# DRV8432_MotorControler.net
KiCad netlist of a schematic drawn in Altium Designer
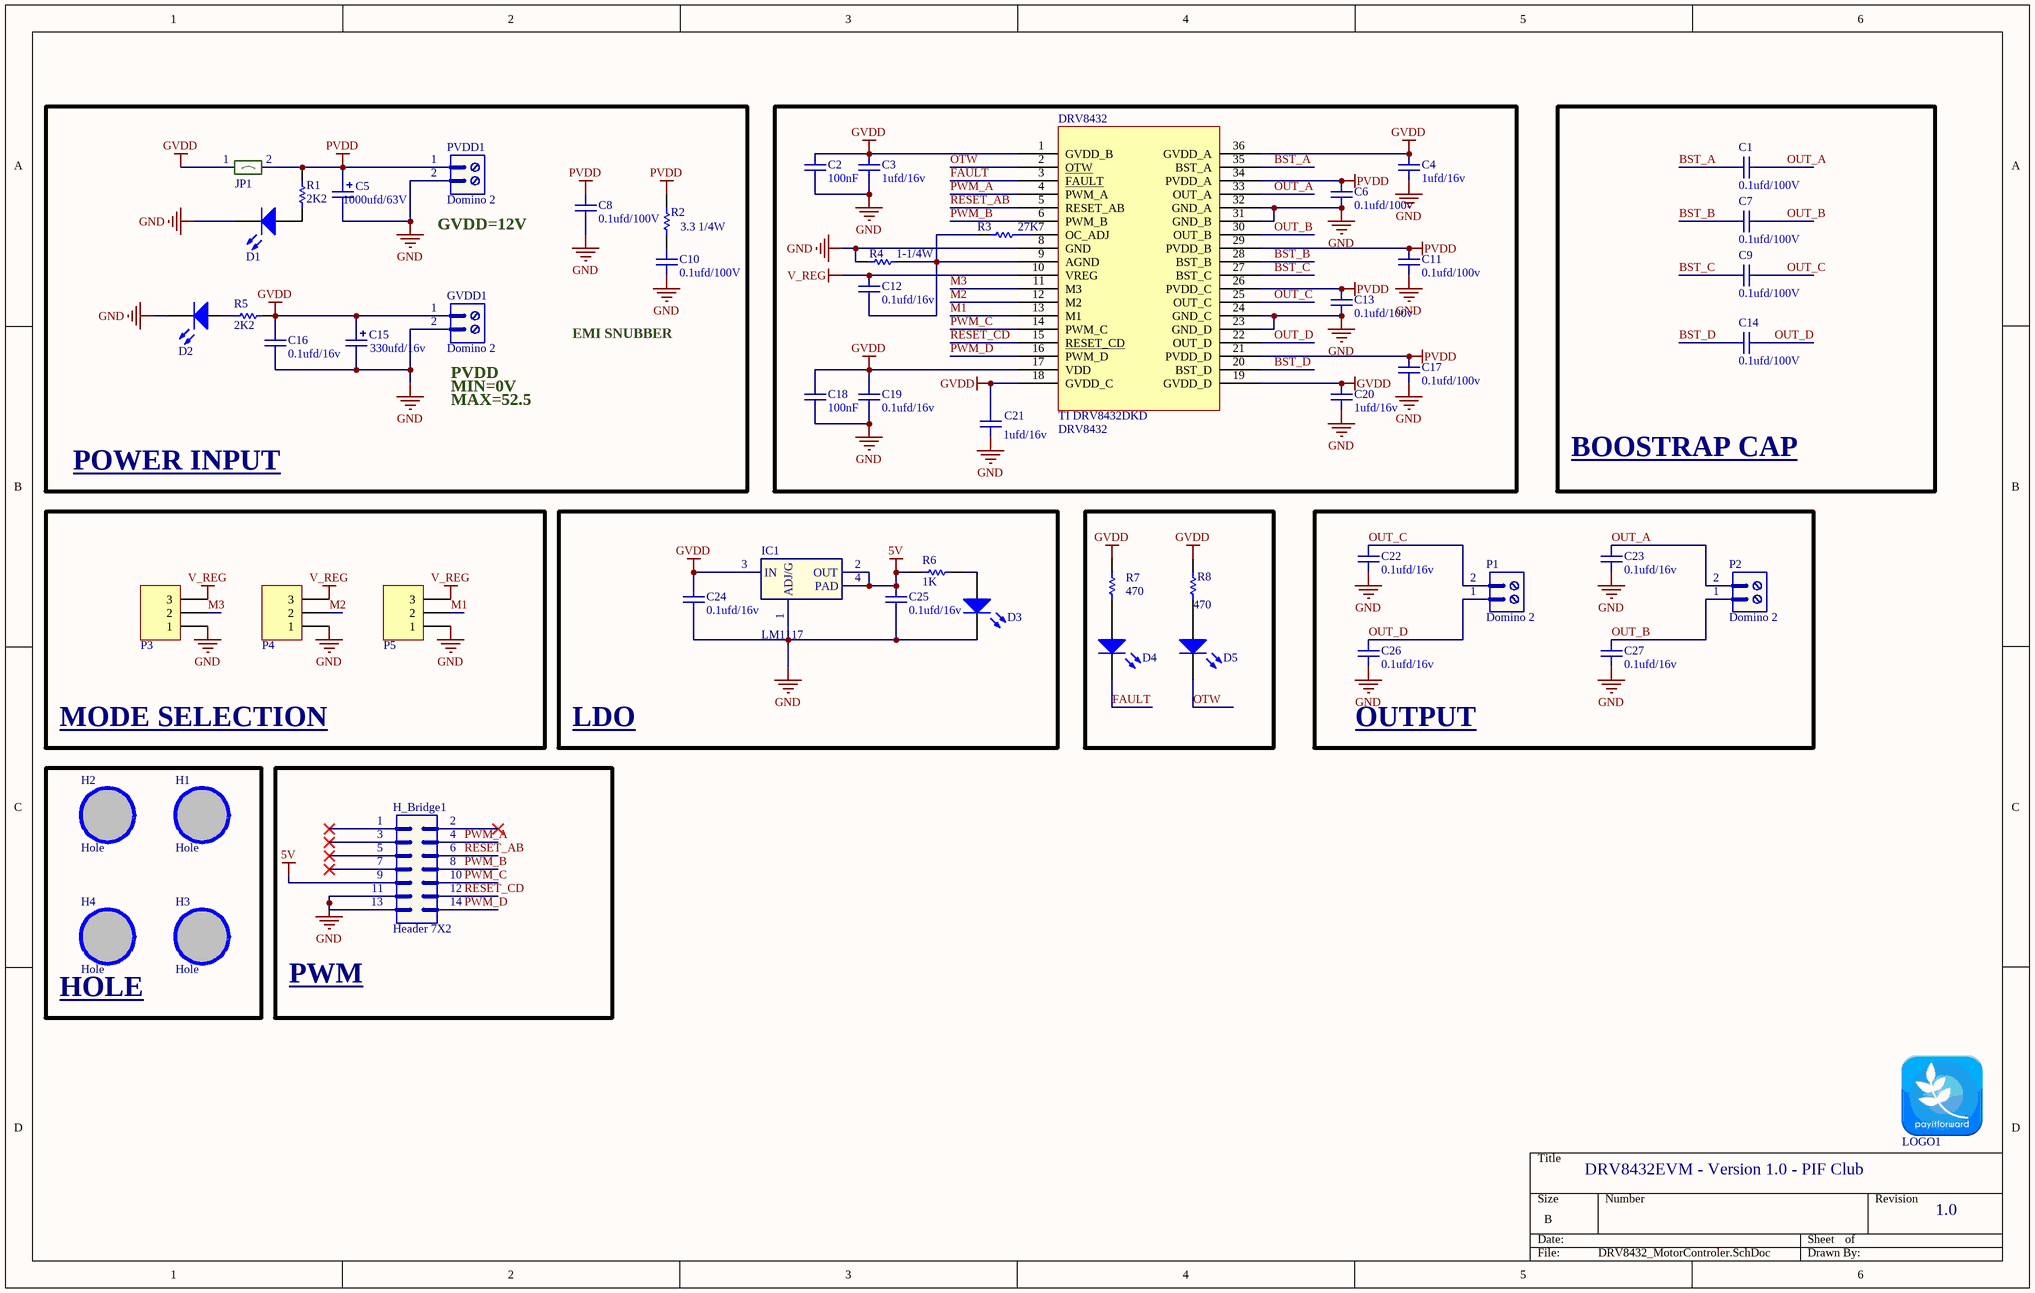
[diagram p0: DRV8432_MotorControler.SchDoc]

(export (version "E")
  (design (tool "Eeschema 10.0.6"))
  (components
    (comp (ref "C1")
      (value "0.1ufd/100V")
      (footprint "CAP-SM-0805")
      (description "Capacitor")
      (fields (field (name "Comment") "Cap Non-Pol SMD"))
      (libsource (lib "minht57_lib") (part "Cap Non-Pol SMD"))
    )
    (comp (ref "C2")
      (value "100nF")
      (footprint "CAP-SM-1210")
      (description "Capacitor")
      (fields (field (name "Comment") "Cap Non-Pol SMD"))
      (libsource (lib "minht57_lib") (part "Cap Non-Pol SMD"))
    )
    (comp (ref "C3")
      (value "1ufd/16v")
      (footprint "CAP-SM-0603")
      (description "Capacitor")
      (fields (field (name "Comment") "Cap Non-Pol SMD"))
      (libsource (lib "minht57_lib") (part "Cap Non-Pol SMD"))
    )
    (comp (ref "C4")
      (value "1ufd/16v")
      (footprint "CAP-SM-0603")
      (description "Capacitor")
      (fields (field (name "Comment") "Cap Non-Pol SMD"))
      (libsource (lib "minht57_lib") (part "Cap Non-Pol SMD"))
    )
    (comp (ref "C5")
      (value "1000ufd/63V")
      (footprint "CP3/7")
      (description "Polarized Capacitor (Radial)")
      (fields (field (name "Comment") "Cap Pol"))
      (libsource (lib "minht57_lib") (part "Cap Pol"))
    )
    (comp (ref "C6")
      (value "0.1ufd/100v")
      (footprint "CAP-SM-0805")
      (description "Capacitor")
      (fields (field (name "Comment") "Cap Non-Pol SMD"))
      (libsource (lib "minht57_lib") (part "Cap Non-Pol SMD"))
    )
    (comp (ref "C7")
      (value "0.1ufd/100V")
      (footprint "CAP-SM-0805")
      (description "Capacitor")
      (fields (field (name "Comment") "Cap Non-Pol SMD"))
      (libsource (lib "minht57_lib") (part "Cap Non-Pol SMD"))
    )
    (comp (ref "C8")
      (value "0.1ufd/100V")
      (footprint "CAP-SM-0805")
      (description "Capacitor")
      (fields (field (name "Comment") "Cap Non-Pol SMD"))
      (libsource (lib "minht57_lib") (part "Cap Non-Pol SMD"))
    )
    (comp (ref "C9")
      (value "0.1ufd/100V")
      (footprint "CAP-SM-0805")
      (description "Capacitor")
      (fields (field (name "Comment") "Cap Non-Pol SMD"))
      (libsource (lib "minht57_lib") (part "Cap Non-Pol SMD"))
    )
    (comp (ref "C10")
      (value "0.1ufd/100V")
      (footprint "CAP-SM-0805")
      (description "Capacitor")
      (fields (field (name "Comment") "Cap Non-Pol SMD"))
      (libsource (lib "minht57_lib") (part "Cap Non-Pol SMD"))
    )
    (comp (ref "C11")
      (value "0.1ufd/100v")
      (footprint "CAP-SM-0805")
      (description "Capacitor")
      (fields (field (name "Comment") "Cap Non-Pol SMD"))
      (libsource (lib "minht57_lib") (part "Cap Non-Pol SMD"))
    )
    (comp (ref "C12")
      (value "0.1ufd/16v")
      (footprint "CAP-SM-0603")
      (description "Capacitor")
      (fields (field (name "Comment") "Cap Non-Pol SMD"))
      (libsource (lib "minht57_lib") (part "Cap Non-Pol SMD"))
    )
    (comp (ref "C13")
      (value "0.1ufd/100v")
      (footprint "CAP-SM-0805")
      (description "Capacitor")
      (fields (field (name "Comment") "Cap Non-Pol SMD"))
      (libsource (lib "minht57_lib") (part "Cap Non-Pol SMD"))
    )
    (comp (ref "C14")
      (value "0.1ufd/100V")
      (footprint "CAP-SM-0805")
      (description "Capacitor")
      (fields (field (name "Comment") "Cap Non-Pol SMD"))
      (libsource (lib "minht57_lib") (part "Cap Non-Pol SMD"))
    )
    (comp (ref "C15")
      (value "330ufd/16v")
      (footprint "CP1/2.5")
      (description "Polarized Capacitor (Radial)")
      (fields (field (name "Comment") "Cap Pol"))
      (libsource (lib "minht57_lib") (part "Cap Pol"))
    )
    (comp (ref "C16")
      (value "0.1ufd/16v")
      (footprint "CAP-SM-0805")
      (description "Capacitor")
      (fields (field (name "Comment") "Cap Non-Pol SMD"))
      (libsource (lib "minht57_lib") (part "Cap Non-Pol SMD"))
    )
    (comp (ref "C17")
      (value "0.1ufd/100v")
      (footprint "CAP-SM-0805")
      (description "Capacitor")
      (fields (field (name "Comment") "Cap Non-Pol SMD"))
      (libsource (lib "minht57_lib") (part "Cap Non-Pol SMD"))
    )
    (comp (ref "C18")
      (value "100nF")
      (footprint "CAP-SM-1210")
      (description "Capacitor")
      (fields (field (name "Comment") "Cap Non-Pol SMD"))
      (libsource (lib "minht57_lib") (part "Cap Non-Pol SMD"))
    )
    (comp (ref "C19")
      (value "0.1ufd/16v")
      (footprint "CAP-SM-0805")
      (description "Capacitor")
      (fields (field (name "Comment") "Cap Non-Pol SMD"))
      (libsource (lib "minht57_lib") (part "Cap Non-Pol SMD"))
    )
    (comp (ref "C20")
      (value "1ufd/16v")
      (footprint "CAP-SM-0603")
      (description "Capacitor")
      (fields (field (name "Comment") "Cap Non-Pol SMD"))
      (libsource (lib "minht57_lib") (part "Cap Non-Pol SMD"))
    )
    (comp (ref "C21")
      (value "1ufd/16v")
      (footprint "CAP-SM-0603")
      (description "Capacitor")
      (fields (field (name "Comment") "Cap Non-Pol SMD"))
      (libsource (lib "minht57_lib") (part "Cap Non-Pol SMD"))
    )
    (comp (ref "C22")
      (value "0.1ufd/16v")
      (footprint "CAP-SM-0805")
      (description "Capacitor")
      (fields (field (name "Comment") "Cap Non-Pol SMD"))
      (libsource (lib "minht57_lib") (part "Cap Non-Pol SMD"))
    )
    (comp (ref "C23")
      (value "0.1ufd/16v")
      (footprint "CAP-SM-0805")
      (description "Capacitor")
      (fields (field (name "Comment") "Cap Non-Pol SMD"))
      (libsource (lib "minht57_lib") (part "Cap Non-Pol SMD"))
    )
    (comp (ref "C24")
      (value "0.1ufd/16v")
      (footprint "CAP-SM-0805")
      (description "Capacitor")
      (fields (field (name "Comment") "Cap Non-Pol SMD"))
      (libsource (lib "minht57_lib") (part "Cap Non-Pol SMD"))
    )
    (comp (ref "C25")
      (value "0.1ufd/16v")
      (footprint "CAP-SM-0805")
      (description "Capacitor")
      (fields (field (name "Comment") "Cap Non-Pol SMD"))
      (libsource (lib "minht57_lib") (part "Cap Non-Pol SMD"))
    )
    (comp (ref "C26")
      (value "0.1ufd/16v")
      (footprint "CAP-SM-0805")
      (description "Capacitor")
      (fields (field (name "Comment") "Cap Non-Pol SMD"))
      (libsource (lib "minht57_lib") (part "Cap Non-Pol SMD"))
    )
    (comp (ref "C27")
      (value "0.1ufd/16v")
      (footprint "CAP-SM-0805")
      (description "Capacitor")
      (fields (field (name "Comment") "Cap Non-Pol SMD"))
      (libsource (lib "minht57_lib") (part "Cap Non-Pol SMD"))
    )
    (comp (ref "D1")
      (value "LED SMD")
      (footprint "LED_0603_Blue")
      (description "LED")
      (libsource (lib "PIF_Library") (part "LED SMD"))
    )
    (comp (ref "D2")
      (value "LED SMD")
      (footprint "LED_0603_Blue")
      (description "LED")
      (libsource (lib "PIF_Library") (part "LED SMD"))
    )
    (comp (ref "D3")
      (value "LED SMD")
      (footprint "LED_0603_Blue")
      (description "LED")
      (libsource (lib "PIF_Library") (part "LED SMD"))
    )
    (comp (ref "D4")
      (value "LED SMD")
      (footprint "LED_0603_Blue")
      (description "LED")
      (libsource (lib "PIF_Library") (part "LED SMD"))
    )
    (comp (ref "D5")
      (value "LED SMD")
      (footprint "LED_0603_Blue")
      (description "LED")
      (libsource (lib "PIF_Library") (part "LED SMD"))
    )
    (comp (ref "DRV8432")
      (value "DRV8432")
      (footprint "PCBComponent_1")
      (libsource (lib "TI_DRV8432") (part "Component_1"))
    )
    (comp (ref "GVDD1")
      (value "Domino 2")
      (footprint "DOMINO 2- 5mm")
      (description "Domino, 2-Pin")
      (fields (field (name "PUBLISHER") "Altium Limited"))
      (libsource (lib "") (part "Domino 2_1"))
    )
    (comp (ref "H1")
      (value "Hole")
      (footprint "LO KHOAN 3MM")
      (description "Hole 3mm")
      (libsource (lib "minht57_lib") (part "Hole"))
    )
    (comp (ref "H2")
      (value "Hole")
      (footprint "LO KHOAN 3MM")
      (description "Hole 3mm")
      (libsource (lib "minht57_lib") (part "Hole"))
    )
    (comp (ref "H3")
      (value "Hole")
      (footprint "LO KHOAN 3MM")
      (description "Hole 3mm")
      (libsource (lib "minht57_lib") (part "Hole"))
    )
    (comp (ref "H4")
      (value "Hole")
      (footprint "LO KHOAN 3MM")
      (description "Hole 3mm")
      (libsource (lib "minht57_lib") (part "Hole"))
    )
    (comp (ref "H_Bridge1")
      (value "Header 7X2")
      (footprint "JP7X2")
      (description "Header, 7-Pin, Dual row")
      (fields (field (name "PUBLISHER") "Altium Limited"))
      (libsource (lib "minht57_lib") (part "Header 7X2"))
    )
    (comp (ref "IC1")
      (value "LM1117")
      (footprint "SOT223-4N")
      (description "Available in 1.8V, 2.5V, 2.85V, 3.3V, 5V, and  Adjustable Versions")
      (libsource (lib "minht57_lib") (part "LM1117"))
    )
    (comp (ref "JP1") (value "Jumper 2") (footprint "JP2") (libsource (lib "minht57_lib") (part "Jumper 2")))
    (comp (ref "LOGO1")
      (value "LOGO PIF")
      (footprint "PIF LOGO TOP OVERLAY")
      (libsource (lib "logo_PIF") (part "LOGO PIF"))
    )
    (comp (ref "P1")
      (value "Domino 2")
      (footprint "DOMINO 2- 5mm")
      (description "Domino, 2-Pin")
      (fields (field (name "PUBLISHER") "Altium Limited"))
      (libsource (lib "minht57_lib") (part "Domino 2"))
    )
    (comp (ref "P2")
      (value "Domino 2")
      (footprint "DOMINO 2- 5mm")
      (description "Domino, 2-Pin")
      (fields (field (name "PUBLISHER") "Altium Limited"))
      (libsource (lib "minht57_lib") (part "Domino 2"))
    )
    (comp (ref "P3")
      (value "Header 3")
      (footprint "JP3")
      (description "Header, 3-Pin")
      (fields (field (name "PUBLISHER") "Altium Limited"))
      (libsource (lib "PIF_Library") (part "Header 3"))
    )
    (comp (ref "P4")
      (value "Header 3")
      (footprint "JP3")
      (description "Header, 3-Pin")
      (fields (field (name "PUBLISHER") "Altium Limited"))
      (libsource (lib "PIF_Library") (part "Header 3"))
    )
    (comp (ref "P5")
      (value "Header 3")
      (footprint "JP3")
      (description "Header, 3-Pin")
      (fields (field (name "PUBLISHER") "Altium Limited"))
      (libsource (lib "PIF_Library") (part "Header 3"))
    )
    (comp (ref "PVDD1")
      (value "Domino 2")
      (footprint "DOMINO 2- 5mm")
      (description "Domino, 2-Pin")
      (fields (field (name "PUBLISHER") "Altium Limited"))
      (libsource (lib "") (part "Domino 2_1"))
    )
    (comp (ref "R1")
      (value "2K2")
      (footprint "RES-SM-0603")
      (description "Resistor")
      (fields (field (name "Comment") "RESISTOR SMD"))
      (libsource (lib "PIF_Library") (part "RESISTOR SMD"))
    )
    (comp (ref "R2")
      (value "3.3 1/4W")
      (footprint "RES-SM-1206")
      (description "Resistor")
      (fields (field (name "Comment") "RESISTOR SMD"))
      (libsource (lib "PIF_Library") (part "RESISTOR SMD"))
    )
    (comp (ref "R3")
      (value "27K")
      (footprint "RES-SM-0603")
      (description "Resistor")
      (fields (field (name "Comment") "RESISTOR SMD"))
      (libsource (lib "PIF_Library") (part "RESISTOR SMD"))
    )
    (comp (ref "R4")
      (value "1-1/4W")
      (footprint "RES-SM-0805")
      (description "Resistor")
      (fields (field (name "Comment") "RESISTOR SMD"))
      (libsource (lib "PIF_Library") (part "RESISTOR SMD"))
    )
    (comp (ref "R5")
      (value "2K2")
      (footprint "RES-SM-0603")
      (description "Resistor")
      (fields (field (name "Comment") "RESISTOR SMD"))
      (libsource (lib "PIF_Library") (part "RESISTOR SMD"))
    )
    (comp (ref "R6")
      (value "1K")
      (footprint "RES-SM-0603")
      (description "Resistor")
      (fields (field (name "Comment") "RESISTOR SMD"))
      (libsource (lib "PIF_Library") (part "RESISTOR SMD"))
    )
    (comp (ref "R7")
      (value "470")
      (footprint "RES-SM-0603")
      (description "Resistor")
      (fields (field (name "Comment") "RESISTOR SMD"))
      (libsource (lib "PIF_Library") (part "RESISTOR SMD"))
    )
    (comp (ref "R8")
      (value "470")
      (footprint "RES-SM-0603")
      (description "Resistor")
      (fields (field (name "Comment") "RESISTOR SMD"))
      (libsource (lib "PIF_Library") (part "RESISTOR SMD"))
    )
  )
  (nets
    (net (code "1") (name "/BST_A") (class "Default")
      (node (ref "C1") (pin "1") (pinfunction "1_1") (pintype "passive"))
      (node (ref "DRV8432") (pin "35") (pinfunction "BST_A_35") (pintype "passive"))
    )
    (net (code "2") (name "/BST_B") (class "Default")
      (node (ref "C7") (pin "1") (pinfunction "1_1") (pintype "passive"))
      (node (ref "DRV8432") (pin "28") (pinfunction "BST_B_28") (pintype "passive"))
    )
    (net (code "3") (name "/BST_C") (class "Default")
      (node (ref "C9") (pin "1") (pinfunction "1_1") (pintype "passive"))
      (node (ref "DRV8432") (pin "27") (pinfunction "BST_C_27") (pintype "passive"))
    )
    (net (code "4") (name "/BST_D") (class "Default")
      (node (ref "C14") (pin "1") (pinfunction "1_1") (pintype "passive"))
      (node (ref "DRV8432") (pin "20") (pinfunction "BST_D_20") (pintype "passive"))
    )
    (net (code "5") (name "/FAULT") (class "Default")
      (node (ref "D4") (pin "2") (pinfunction "K_2") (pintype "passive"))
      (node (ref "DRV8432") (pin "3") (pinfunction "FAULT_3") (pintype "passive"))
    )
    (net (code "6") (name "/M1") (class "Default")
      (node (ref "DRV8432") (pin "13") (pinfunction "M1_13") (pintype "passive"))
      (node (ref "P5") (pin "2") (pinfunction "2_2") (pintype "passive"))
    )
    (net (code "7") (name "/M2") (class "Default")
      (node (ref "DRV8432") (pin "12") (pinfunction "M2_12") (pintype "passive"))
      (node (ref "P4") (pin "2") (pinfunction "2_2") (pintype "passive"))
    )
    (net (code "8") (name "/M3") (class "Default")
      (node (ref "DRV8432") (pin "11") (pinfunction "M3_11") (pintype "passive"))
      (node (ref "P3") (pin "2") (pinfunction "2_2") (pintype "passive"))
    )
    (net (code "9") (name "/OTW") (class "Default")
      (node (ref "D5") (pin "2") (pinfunction "K_2") (pintype "passive"))
      (node (ref "DRV8432") (pin "2") (pinfunction "OTW_2") (pintype "passive"))
    )
    (net (code "10") (name "/OUT_A") (class "Default")
      (node (ref "C1") (pin "2") (pinfunction "2_2") (pintype "passive"))
      (node (ref "C23") (pin "2") (pinfunction "2_2") (pintype "passive"))
      (node (ref "DRV8432") (pin "33") (pinfunction "OUT_A_33") (pintype "passive"))
      (node (ref "P2") (pin "2") (pinfunction "2_2") (pintype "passive"))
    )
    (net (code "11") (name "/OUT_B") (class "Default")
      (node (ref "C27") (pin "2") (pinfunction "2_2") (pintype "passive"))
      (node (ref "C7") (pin "2") (pinfunction "2_2") (pintype "passive"))
      (node (ref "DRV8432") (pin "30") (pinfunction "OUT_B_30") (pintype "passive"))
      (node (ref "P2") (pin "1") (pinfunction "1_1") (pintype "passive"))
    )
    (net (code "12") (name "/OUT_C") (class "Default")
      (node (ref "C22") (pin "2") (pinfunction "2_2") (pintype "passive"))
      (node (ref "C9") (pin "2") (pinfunction "2_2") (pintype "passive"))
      (node (ref "DRV8432") (pin "25") (pinfunction "OUT_C_25") (pintype "passive"))
      (node (ref "P1") (pin "2") (pinfunction "2_2") (pintype "passive"))
    )
    (net (code "13") (name "/OUT_D") (class "Default")
      (node (ref "C14") (pin "2") (pinfunction "2_2") (pintype "passive"))
      (node (ref "C26") (pin "2") (pinfunction "2_2") (pintype "passive"))
      (node (ref "DRV8432") (pin "22") (pinfunction "OUT_D_22") (pintype "passive"))
      (node (ref "P1") (pin "1") (pinfunction "1_1") (pintype "passive"))
    )
    (net (code "14") (name "/PWM_A") (class "Default")
      (node (ref "DRV8432") (pin "4") (pinfunction "PWM_A_4") (pintype "passive"))
      (node (ref "H_Bridge1") (pin "4") (pinfunction "4_4") (pintype "passive"))
    )
    (net (code "15") (name "/PWM_B") (class "Default")
      (node (ref "DRV8432") (pin "6") (pinfunction "PWM_B_6") (pintype "passive"))
      (node (ref "H_Bridge1") (pin "8") (pinfunction "8_8") (pintype "passive"))
    )
    (net (code "16") (name "/PWM_C") (class "Default")
      (node (ref "DRV8432") (pin "14") (pinfunction "PWM_C_14") (pintype "passive"))
      (node (ref "H_Bridge1") (pin "10") (pinfunction "10_10") (pintype "passive"))
    )
    (net (code "17") (name "/PWM_D") (class "Default")
      (node (ref "DRV8432") (pin "16") (pinfunction "PWM_D_16") (pintype "passive"))
      (node (ref "H_Bridge1") (pin "14") (pinfunction "14_14") (pintype "passive"))
    )
    (net (code "18") (name "/RESET_AB") (class "Default")
      (node (ref "DRV8432") (pin "5") (pinfunction "RESET_AB_5") (pintype "passive"))
      (node (ref "H_Bridge1") (pin "6") (pinfunction "6_6") (pintype "passive"))
    )
    (net (code "19") (name "/RESET_CD") (class "Default")
      (node (ref "DRV8432") (pin "15") (pinfunction "RESET_CD_15") (pintype "passive"))
      (node (ref "H_Bridge1") (pin "12") (pinfunction "12_12") (pintype "passive"))
    )
    (net (code "20") (name "5V") (class "Default")
      (node (ref "C25") (pin "2") (pinfunction "2_2") (pintype "passive"))
      (node (ref "H_Bridge1") (pin "9") (pinfunction "9_9") (pintype "passive"))
      (node (ref "IC1") (pin "2") (pinfunction "OUT_2") (pintype "passive"))
      (node (ref "IC1") (pin "4") (pinfunction "PAD_4") (pintype "passive"))
      (node (ref "R6") (pin "2") (pinfunction "2_2") (pintype "passive"))
    )
    (net (code "21") (name "GND") (class "Default")
      (node (ref "C10") (pin "1") (pinfunction "1_1") (pintype "passive"))
      (node (ref "C11") (pin "1") (pinfunction "1_1") (pintype "passive"))
      (node (ref "C13") (pin "1") (pinfunction "1_1") (pintype "passive"))
      (node (ref "C15") (pin "2") (pinfunction "2_2") (pintype "passive"))
      (node (ref "C16") (pin "1") (pinfunction "1_1") (pintype "passive"))
      (node (ref "C17") (pin "1") (pinfunction "1_1") (pintype "passive"))
      (node (ref "C18") (pin "1") (pinfunction "1_1") (pintype "passive"))
      (node (ref "C19") (pin "1") (pinfunction "1_1") (pintype "passive"))
      (node (ref "C2") (pin "1") (pinfunction "1_1") (pintype "passive"))
      (node (ref "C20") (pin "1") (pinfunction "1_1") (pintype "passive"))
      (node (ref "C21") (pin "1") (pinfunction "1_1") (pintype "passive"))
      (node (ref "C22") (pin "1") (pinfunction "1_1") (pintype "passive"))
      (node (ref "C23") (pin "1") (pinfunction "1_1") (pintype "passive"))
      (node (ref "C24") (pin "1") (pinfunction "1_1") (pintype "passive"))
      (node (ref "C25") (pin "1") (pinfunction "1_1") (pintype "passive"))
      (node (ref "C26") (pin "1") (pinfunction "1_1") (pintype "passive"))
      (node (ref "C27") (pin "1") (pinfunction "1_1") (pintype "passive"))
      (node (ref "C3") (pin "2") (pinfunction "2_2") (pintype "passive"))
      (node (ref "C4") (pin "2") (pinfunction "2_2") (pintype "passive"))
      (node (ref "C5") (pin "2") (pinfunction "2_2") (pintype "passive"))
      (node (ref "C6") (pin "1") (pinfunction "1_1") (pintype "passive"))
      (node (ref "C8") (pin "1") (pinfunction "1_1") (pintype "passive"))
      (node (ref "D1") (pin "2") (pinfunction "K_2") (pintype "passive"))
      (node (ref "D2") (pin "2") (pinfunction "K_2") (pintype "passive"))
      (node (ref "D3") (pin "2") (pinfunction "K_2") (pintype "passive"))
      (node (ref "DRV8432") (pin "23") (pinfunction "GND_D_23") (pintype "passive"))
      (node (ref "DRV8432") (pin "24") (pinfunction "GND_C_24") (pintype "passive"))
      (node (ref "DRV8432") (pin "31") (pinfunction "GND_B_31") (pintype "passive"))
      (node (ref "DRV8432") (pin "32") (pinfunction "GND_A_32") (pintype "passive"))
      (node (ref "DRV8432") (pin "8") (pinfunction "GND_8") (pintype "passive"))
      (node (ref "GVDD1") (pin "2") (pinfunction "2_2") (pintype "passive"))
      (node (ref "H_Bridge1") (pin "11") (pinfunction "11_11") (pintype "passive"))
      (node (ref "H_Bridge1") (pin "13") (pinfunction "13_13") (pintype "passive"))
      (node (ref "IC1") (pin "1") (pinfunction "ADJ/G_1") (pintype "passive"))
      (node (ref "P3") (pin "1") (pinfunction "1_1") (pintype "passive"))
      (node (ref "P4") (pin "1") (pinfunction "1_1") (pintype "passive"))
      (node (ref "P5") (pin "1") (pinfunction "1_1") (pintype "passive"))
      (node (ref "PVDD1") (pin "2") (pinfunction "2_2") (pintype "passive"))
      (node (ref "R4") (pin "2") (pinfunction "2_2") (pintype "passive"))
    )
    (net (code "22") (name "GVDD") (class "Default")
      (node (ref "C15") (pin "1") (pinfunction "1_1") (pintype "passive"))
      (node (ref "C16") (pin "2") (pinfunction "2_2") (pintype "passive"))
      (node (ref "C18") (pin "2") (pinfunction "2_2") (pintype "passive"))
      (node (ref "C19") (pin "2") (pinfunction "2_2") (pintype "passive"))
      (node (ref "C2") (pin "2") (pinfunction "2_2") (pintype "passive"))
      (node (ref "C20") (pin "2") (pinfunction "2_2") (pintype "passive"))
      (node (ref "C21") (pin "2") (pinfunction "2_2") (pintype "passive"))
      (node (ref "C24") (pin "2") (pinfunction "2_2") (pintype "passive"))
      (node (ref "C3") (pin "1") (pinfunction "1_1") (pintype "passive"))
      (node (ref "C4") (pin "1") (pinfunction "1_1") (pintype "passive"))
      (node (ref "DRV8432") (pin "1") (pinfunction "GVDD_B_1") (pintype "passive"))
      (node (ref "DRV8432") (pin "17") (pinfunction "VDD_17") (pintype "passive"))
      (node (ref "DRV8432") (pin "18") (pinfunction "GVDD_C_18") (pintype "passive"))
      (node (ref "DRV8432") (pin "19") (pinfunction "GVDD_D_19") (pintype "passive"))
      (node (ref "DRV8432") (pin "36") (pinfunction "GVDD_A_36") (pintype "passive"))
      (node (ref "GVDD1") (pin "1") (pinfunction "1_1") (pintype "passive"))
      (node (ref "IC1") (pin "3") (pinfunction "IN_3") (pintype "passive"))
      (node (ref "JP1") (pin "1") (pinfunction "1_1") (pintype "passive"))
      (node (ref "R5") (pin "2") (pinfunction "2_2") (pintype "passive"))
      (node (ref "R7") (pin "2") (pinfunction "2_2") (pintype "passive"))
      (node (ref "R8") (pin "2") (pinfunction "2_2") (pintype "passive"))
    )
    (net (code "23") (name "Net-(C10-Pad2)") (class "Default")
      (node (ref "C10") (pin "2") (pinfunction "2_2") (pintype "passive"))
      (node (ref "R2") (pin "1") (pinfunction "1_1") (pintype "passive"))
    )
    (net (code "24") (name "Net-(D1-A)") (class "Default")
      (node (ref "D1") (pin "1") (pinfunction "A_1") (pintype "passive"))
      (node (ref "R1") (pin "1") (pinfunction "1_1") (pintype "passive"))
    )
    (net (code "25") (name "Net-(D2-A)") (class "Default")
      (node (ref "D2") (pin "1") (pinfunction "A_1") (pintype "passive"))
      (node (ref "R5") (pin "1") (pinfunction "1_1") (pintype "passive"))
    )
    (net (code "26") (name "Net-(D3-A)") (class "Default")
      (node (ref "D3") (pin "1") (pinfunction "A_1") (pintype "passive"))
      (node (ref "R6") (pin "1") (pinfunction "1_1") (pintype "passive"))
    )
    (net (code "27") (name "Net-(D4-A)") (class "Default")
      (node (ref "D4") (pin "1") (pinfunction "A_1") (pintype "passive"))
      (node (ref "R7") (pin "1") (pinfunction "1_1") (pintype "passive"))
    )
    (net (code "28") (name "Net-(D5-A)") (class "Default")
      (node (ref "D5") (pin "1") (pinfunction "A_1") (pintype "passive"))
      (node (ref "R8") (pin "1") (pinfunction "1_1") (pintype "passive"))
    )
    (net (code "29") (name "Net-(DRV8432-AGND)") (class "Default")
      (node (ref "C12") (pin "2") (pinfunction "2_2") (pintype "passive"))
      (node (ref "DRV8432") (pin "9") (pinfunction "AGND_9") (pintype "passive"))
      (node (ref "R3") (pin "2") (pinfunction "2_2") (pintype "passive"))
      (node (ref "R4") (pin "1") (pinfunction "1_1") (pintype "passive"))
    )
    (net (code "30") (name "Net-(DRV8432-OC_ADJ)") (class "Default")
      (node (ref "DRV8432") (pin "7") (pinfunction "OC_ADJ_7") (pintype "passive"))
      (node (ref "R3") (pin "1") (pinfunction "1_1") (pintype "passive"))
    )
    (net (code "31") (name "PVDD") (class "Default")
      (node (ref "C11") (pin "2") (pinfunction "2_2") (pintype "passive"))
      (node (ref "C13") (pin "2") (pinfunction "2_2") (pintype "passive"))
      (node (ref "C17") (pin "2") (pinfunction "2_2") (pintype "passive"))
      (node (ref "C5") (pin "1") (pinfunction "1_1") (pintype "passive"))
      (node (ref "C6") (pin "2") (pinfunction "2_2") (pintype "passive"))
      (node (ref "C8") (pin "2") (pinfunction "2_2") (pintype "passive"))
      (node (ref "DRV8432") (pin "21") (pinfunction "PVDD_D_21") (pintype "passive"))
      (node (ref "DRV8432") (pin "26") (pinfunction "PVDD_C_26") (pintype "passive"))
      (node (ref "DRV8432") (pin "29") (pinfunction "PVDD_B_29") (pintype "passive"))
      (node (ref "DRV8432") (pin "34") (pinfunction "PVDD_A_34") (pintype "passive"))
      (node (ref "JP1") (pin "2") (pinfunction "2_2") (pintype "passive"))
      (node (ref "PVDD1") (pin "1") (pinfunction "1_1") (pintype "passive"))
      (node (ref "R1") (pin "2") (pinfunction "2_2") (pintype "passive"))
      (node (ref "R2") (pin "2") (pinfunction "2_2") (pintype "passive"))
    )
    (net (code "32") (name "V_REG") (class "Default")
      (node (ref "C12") (pin "1") (pinfunction "1_1") (pintype "passive"))
      (node (ref "DRV8432") (pin "10") (pinfunction "VREG_10") (pintype "passive"))
      (node (ref "P3") (pin "3") (pinfunction "3_3") (pintype "passive"))
      (node (ref "P4") (pin "3") (pinfunction "3_3") (pintype "passive"))
      (node (ref "P5") (pin "3") (pinfunction "3_3") (pintype "passive"))
    )
    (net (code "33") (name "unconnected-(H1-Pad1)") (class "Default")
      (node (ref "H1") (pin "1") (pinfunction "1_1") (pintype "passive"))
    )
    (net (code "34") (name "unconnected-(H2-Pad1)") (class "Default")
      (node (ref "H2") (pin "1") (pinfunction "1_1") (pintype "passive"))
    )
    (net (code "35") (name "unconnected-(H3-Pad1)") (class "Default")
      (node (ref "H3") (pin "1") (pinfunction "1_1") (pintype "passive"))
    )
    (net (code "36") (name "unconnected-(H4-Pad1)") (class "Default")
      (node (ref "H4") (pin "1") (pinfunction "1_1") (pintype "passive"))
    )
    (net (code "37") (name "unconnected-(H_Bridge1-Pad1)") (class "Default")
      (node (ref "H_Bridge1") (pin "1") (pinfunction "1_1") (pintype "passive+no_connect"))
    )
    (net (code "38") (name "unconnected-(H_Bridge1-Pad2)") (class "Default")
      (node (ref "H_Bridge1") (pin "2") (pinfunction "2_2") (pintype "passive+no_connect"))
    )
    (net (code "39") (name "unconnected-(H_Bridge1-Pad3)") (class "Default")
      (node (ref "H_Bridge1") (pin "3") (pinfunction "3_3") (pintype "passive+no_connect"))
    )
    (net (code "40") (name "unconnected-(H_Bridge1-Pad5)") (class "Default")
      (node (ref "H_Bridge1") (pin "5") (pinfunction "5_5") (pintype "passive+no_connect"))
    )
    (net (code "41") (name "unconnected-(H_Bridge1-Pad7)") (class "Default")
      (node (ref "H_Bridge1") (pin "7") (pinfunction "7_7") (pintype "passive+no_connect"))
    )
  )
)
